# Nusbio1_0_WaveShare_I2C_LCD.net
KiCad netlist of a schematic drawn in EAGLE
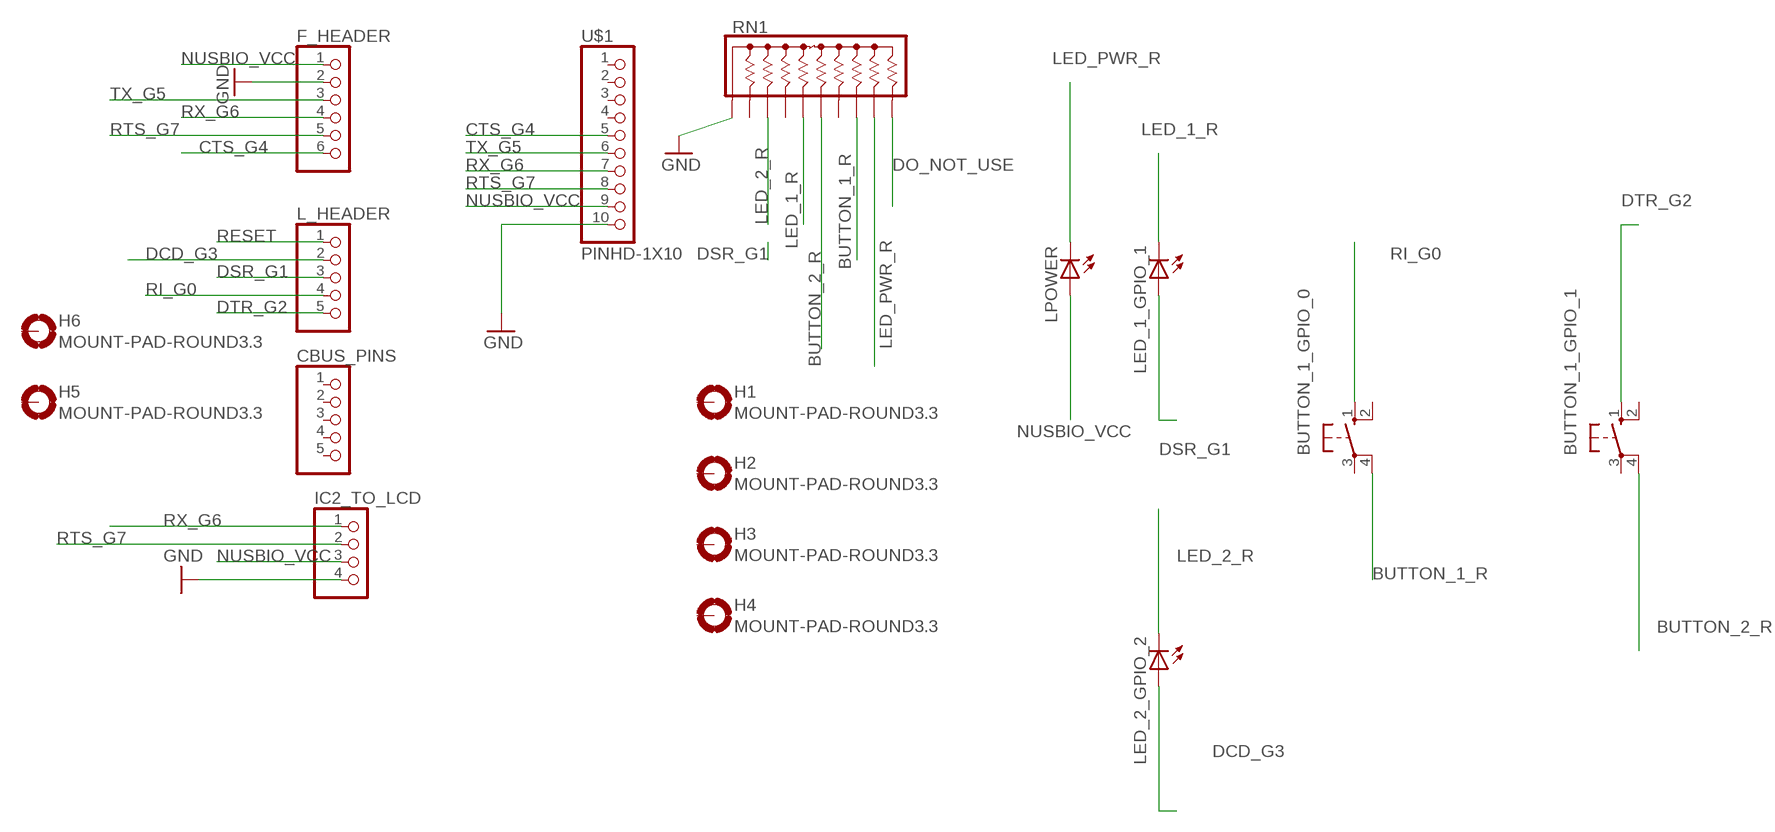
[diagram p0: schematic, sheet 1]

(export (version "E")
  (design (tool "Eeschema 10.0.6"))
  (components
    (comp (ref "BUTTON_1_GPIO_0")
      (value "10-XX")
      (footprint "eagle-import:B3F-10XX")
      (fields (field (name "MPN") "B3F-1000"))
      (libsource (lib "eagle-import") (part "10-XX"))
    )
    (comp (ref "BUTTON_1_GPIO_1")
      (value "10-XX")
      (footprint "eagle-import:B3F-10XX")
      (fields (field (name "MPN") "B3F-1000"))
      (libsource (lib "eagle-import") (part "10-XX"))
    )
    (comp (ref "CBUS_PINS")
      (value "PINHD-1X5")
      (footprint "eagle-import:1X05")
      (libsource (lib "eagle-import") (part "PINHD-1X5"))
    )
    (comp (ref "F_HEADER")
      (value "PINHD-1X6")
      (footprint "eagle-import:1X06")
      (libsource (lib "eagle-import") (part "PINHD-1X6"))
    )
    (comp (ref "H1")
      (value "MOUNT-PAD-ROUND3.3")
      (footprint "eagle-import:3,3-PAD")
      (libsource (lib "eagle-import") (part "MOUNT-PAD-ROUND3.3"))
    )
    (comp (ref "H2")
      (value "MOUNT-PAD-ROUND3.3")
      (footprint "eagle-import:3,3-PAD")
      (libsource (lib "eagle-import") (part "MOUNT-PAD-ROUND3.3"))
    )
    (comp (ref "H3")
      (value "MOUNT-PAD-ROUND3.3")
      (footprint "eagle-import:3,3-PAD")
      (libsource (lib "eagle-import") (part "MOUNT-PAD-ROUND3.3"))
    )
    (comp (ref "H4")
      (value "MOUNT-PAD-ROUND3.3")
      (footprint "eagle-import:3,3-PAD")
      (libsource (lib "eagle-import") (part "MOUNT-PAD-ROUND3.3"))
    )
    (comp (ref "H5")
      (value "MOUNT-PAD-ROUND3.3")
      (footprint "eagle-import:3,3-PAD")
      (libsource (lib "eagle-import") (part "MOUNT-PAD-ROUND3.3"))
    )
    (comp (ref "H6")
      (value "MOUNT-PAD-ROUND3.3")
      (footprint "eagle-import:3,3-PAD")
      (libsource (lib "eagle-import") (part "MOUNT-PAD-ROUND3.3"))
    )
    (comp (ref "IC2_TO_LCD")
      (value "PINHD-1X4")
      (footprint "eagle-import:1X04")
      (libsource (lib "eagle-import") (part "PINHD-1X4"))
    )
    (comp (ref "LED_1_GPIO_1")
      (value "LEDSMT1206")
      (footprint "eagle-import:1206")
      (libsource (lib "eagle-import") (part "LEDSMT1206"))
    )
    (comp (ref "LED_2_GPIO_2")
      (value "LEDSMT1206")
      (footprint "eagle-import:1206")
      (libsource (lib "eagle-import") (part "LEDSMT1206"))
    )
    (comp (ref "LPOWER")
      (value "LEDSMT1206")
      (footprint "eagle-import:1206")
      (libsource (lib "eagle-import") (part "LEDSMT1206"))
    )
    (comp (ref "L_HEADER")
      (value "PINHD-1X5")
      (footprint "eagle-import:1X05")
      (libsource (lib "eagle-import") (part "PINHD-1X5"))
    )
    (comp (ref "RN1")
      (value "4610X")
      (footprint "eagle-import:SIP10")
      (libsource (lib "eagle-import") (part "4610X"))
    )
    (comp (ref "U$1")
      (value "PINHD-1X10")
      (footprint "eagle-import:1X10-BIG")
      (libsource (lib "eagle-import") (part "PINHD-1X10"))
    )
  )
  (nets
    (net (code "1") (name "/BUTTON_1_R") (class "Default")
      (node (ref "BUTTON_1_GPIO_0") (pin "4") (pinfunction "P1_4") (pintype "passive"))
      (node (ref "RN1") (pin "8") (pinfunction "8_8") (pintype "passive"))
    )
    (net (code "2") (name "/BUTTON_2_R") (class "Default")
      (node (ref "BUTTON_1_GPIO_1") (pin "4") (pinfunction "P1_4") (pintype "passive"))
      (node (ref "RN1") (pin "6") (pinfunction "6_6") (pintype "passive"))
    )
    (net (code "3") (name "/CTS_G4") (class "Default")
      (node (ref "F_HEADER") (pin "6") (pinfunction "6_6") (pintype "passive"))
      (node (ref "U$1") (pin "5") (pinfunction "5_5") (pintype "passive"))
    )
    (net (code "4") (name "/DCD_G3") (class "Default")
      (node (ref "LED_2_GPIO_2") (pin "A") (pinfunction "A_A") (pintype "passive"))
      (node (ref "L_HEADER") (pin "2") (pinfunction "2_2") (pintype "passive"))
    )
    (net (code "5") (name "/DO_NOT_USE") (class "Default")
      (node (ref "RN1") (pin "10") (pinfunction "10_10") (pintype "passive"))
    )
    (net (code "6") (name "/DSR_G1") (class "Default")
      (node (ref "LED_1_GPIO_1") (pin "A") (pinfunction "A_A") (pintype "passive"))
      (node (ref "L_HEADER") (pin "3") (pinfunction "3_3") (pintype "passive"))
    )
    (net (code "7") (name "/DTR_G2") (class "Default")
      (node (ref "BUTTON_1_GPIO_1") (pin "1") (pinfunction "S_1") (pintype "passive"))
      (node (ref "L_HEADER") (pin "5") (pinfunction "5_5") (pintype "passive"))
    )
    (net (code "8") (name "/LED_1_R") (class "Default")
      (node (ref "LED_1_GPIO_1") (pin "C") (pinfunction "C_C") (pintype "passive"))
      (node (ref "RN1") (pin "5") (pinfunction "5_5") (pintype "passive"))
    )
    (net (code "9") (name "/LED_2_R") (class "Default")
      (node (ref "LED_2_GPIO_2") (pin "C") (pinfunction "C_C") (pintype "passive"))
      (node (ref "RN1") (pin "3") (pinfunction "3_3") (pintype "passive"))
    )
    (net (code "10") (name "/LED_PWR_R") (class "Default")
      (node (ref "LPOWER") (pin "C") (pinfunction "C_C") (pintype "passive"))
      (node (ref "RN1") (pin "9") (pinfunction "9_9") (pintype "passive"))
    )
    (net (code "11") (name "/NUSBIO_VCC") (class "Default")
      (node (ref "F_HEADER") (pin "1") (pinfunction "1_1") (pintype "passive"))
      (node (ref "IC2_TO_LCD") (pin "3") (pinfunction "3_3") (pintype "passive"))
      (node (ref "LPOWER") (pin "A") (pinfunction "A_A") (pintype "passive"))
      (node (ref "U$1") (pin "9") (pinfunction "9_9") (pintype "passive"))
    )
    (net (code "12") (name "/RESET") (class "Default")
      (node (ref "L_HEADER") (pin "1") (pinfunction "1_1") (pintype "passive"))
    )
    (net (code "13") (name "/RI_G0") (class "Default")
      (node (ref "BUTTON_1_GPIO_0") (pin "1") (pinfunction "S_1") (pintype "passive"))
      (node (ref "L_HEADER") (pin "4") (pinfunction "4_4") (pintype "passive"))
    )
    (net (code "14") (name "/RTS_G7") (class "Default")
      (node (ref "F_HEADER") (pin "5") (pinfunction "5_5") (pintype "passive"))
      (node (ref "IC2_TO_LCD") (pin "2") (pinfunction "2_2") (pintype "passive"))
      (node (ref "U$1") (pin "8") (pinfunction "8_8") (pintype "passive"))
    )
    (net (code "15") (name "/RX_G6") (class "Default")
      (node (ref "F_HEADER") (pin "4") (pinfunction "4_4") (pintype "passive"))
      (node (ref "IC2_TO_LCD") (pin "1") (pinfunction "1_1") (pintype "passive"))
      (node (ref "U$1") (pin "7") (pinfunction "7_7") (pintype "passive"))
    )
    (net (code "16") (name "/TX_G5") (class "Default")
      (node (ref "F_HEADER") (pin "3") (pinfunction "3_3") (pintype "passive"))
      (node (ref "U$1") (pin "6") (pinfunction "6_6") (pintype "passive"))
    )
    (net (code "17") (name "GND") (class "Default")
      (node (ref "F_HEADER") (pin "2") (pinfunction "2_2") (pintype "passive"))
      (node (ref "IC2_TO_LCD") (pin "4") (pinfunction "4_4") (pintype "passive"))
      (node (ref "RN1") (pin "1") (pinfunction "1_1") (pintype "passive"))
      (node (ref "U$1") (pin "10") (pinfunction "10_10") (pintype "passive"))
    )
    (net (code "18") (name "unconnected-(BUTTON_1_GPIO_0-P-Pad3)") (class "Default")
      (node (ref "BUTTON_1_GPIO_0") (pin "3") (pinfunction "P_3") (pintype "passive"))
    )
    (net (code "19") (name "unconnected-(BUTTON_1_GPIO_0-S1-Pad2)") (class "Default")
      (node (ref "BUTTON_1_GPIO_0") (pin "2") (pinfunction "S1_2") (pintype "passive"))
    )
    (net (code "20") (name "unconnected-(BUTTON_1_GPIO_1-P-Pad3)") (class "Default")
      (node (ref "BUTTON_1_GPIO_1") (pin "3") (pinfunction "P_3") (pintype "passive"))
    )
    (net (code "21") (name "unconnected-(BUTTON_1_GPIO_1-S1-Pad2)") (class "Default")
      (node (ref "BUTTON_1_GPIO_1") (pin "2") (pinfunction "S1_2") (pintype "passive"))
    )
    (net (code "22") (name "unconnected-(CBUS_PINS-Pad1)") (class "Default")
      (node (ref "CBUS_PINS") (pin "1") (pinfunction "1_1") (pintype "passive"))
    )
    (net (code "23") (name "unconnected-(CBUS_PINS-Pad2)") (class "Default")
      (node (ref "CBUS_PINS") (pin "2") (pinfunction "2_2") (pintype "passive"))
    )
    (net (code "24") (name "unconnected-(CBUS_PINS-Pad3)") (class "Default")
      (node (ref "CBUS_PINS") (pin "3") (pinfunction "3_3") (pintype "passive"))
    )
    (net (code "25") (name "unconnected-(CBUS_PINS-Pad4)") (class "Default")
      (node (ref "CBUS_PINS") (pin "4") (pinfunction "4_4") (pintype "passive"))
    )
    (net (code "26") (name "unconnected-(CBUS_PINS-Pad5)") (class "Default")
      (node (ref "CBUS_PINS") (pin "5") (pinfunction "5_5") (pintype "passive"))
    )
    (net (code "27") (name "unconnected-(H1-MOUNT-PadB3,3)") (class "Default")
      (node (ref "H1") (pin "B3,3") (pinfunction "MOUNT_B3,3") (pintype "passive"))
    )
    (net (code "28") (name "unconnected-(H2-MOUNT-PadB3,3)") (class "Default")
      (node (ref "H2") (pin "B3,3") (pinfunction "MOUNT_B3,3") (pintype "passive"))
    )
    (net (code "29") (name "unconnected-(H3-MOUNT-PadB3,3)") (class "Default")
      (node (ref "H3") (pin "B3,3") (pinfunction "MOUNT_B3,3") (pintype "passive"))
    )
    (net (code "30") (name "unconnected-(H4-MOUNT-PadB3,3)") (class "Default")
      (node (ref "H4") (pin "B3,3") (pinfunction "MOUNT_B3,3") (pintype "passive"))
    )
    (net (code "31") (name "unconnected-(H5-MOUNT-PadB3,3)") (class "Default")
      (node (ref "H5") (pin "B3,3") (pinfunction "MOUNT_B3,3") (pintype "passive"))
    )
    (net (code "32") (name "unconnected-(H6-MOUNT-PadB3,3)") (class "Default")
      (node (ref "H6") (pin "B3,3") (pinfunction "MOUNT_B3,3") (pintype "passive"))
    )
    (net (code "33") (name "unconnected-(RN1-Pad2)") (class "Default")
      (node (ref "RN1") (pin "2") (pinfunction "2_2") (pintype "passive"))
    )
    (net (code "34") (name "unconnected-(RN1-Pad4)") (class "Default")
      (node (ref "RN1") (pin "4") (pinfunction "4_4") (pintype "passive"))
    )
    (net (code "35") (name "unconnected-(RN1-Pad7)") (class "Default")
      (node (ref "RN1") (pin "7") (pinfunction "7_7") (pintype "passive"))
    )
    (net (code "36") (name "unconnected-(U$1-Pad1)") (class "Default")
      (node (ref "U$1") (pin "1") (pinfunction "1_1") (pintype "passive"))
    )
    (net (code "37") (name "unconnected-(U$1-Pad2)") (class "Default")
      (node (ref "U$1") (pin "2") (pinfunction "2_2") (pintype "passive"))
    )
    (net (code "38") (name "unconnected-(U$1-Pad3)") (class "Default")
      (node (ref "U$1") (pin "3") (pinfunction "3_3") (pintype "passive"))
    )
    (net (code "39") (name "unconnected-(U$1-Pad4)") (class "Default")
      (node (ref "U$1") (pin "4") (pinfunction "4_4") (pintype "passive"))
    )
  )
)
